# mdbt40.net
KiCad netlist of a schematic drawn in EAGLE
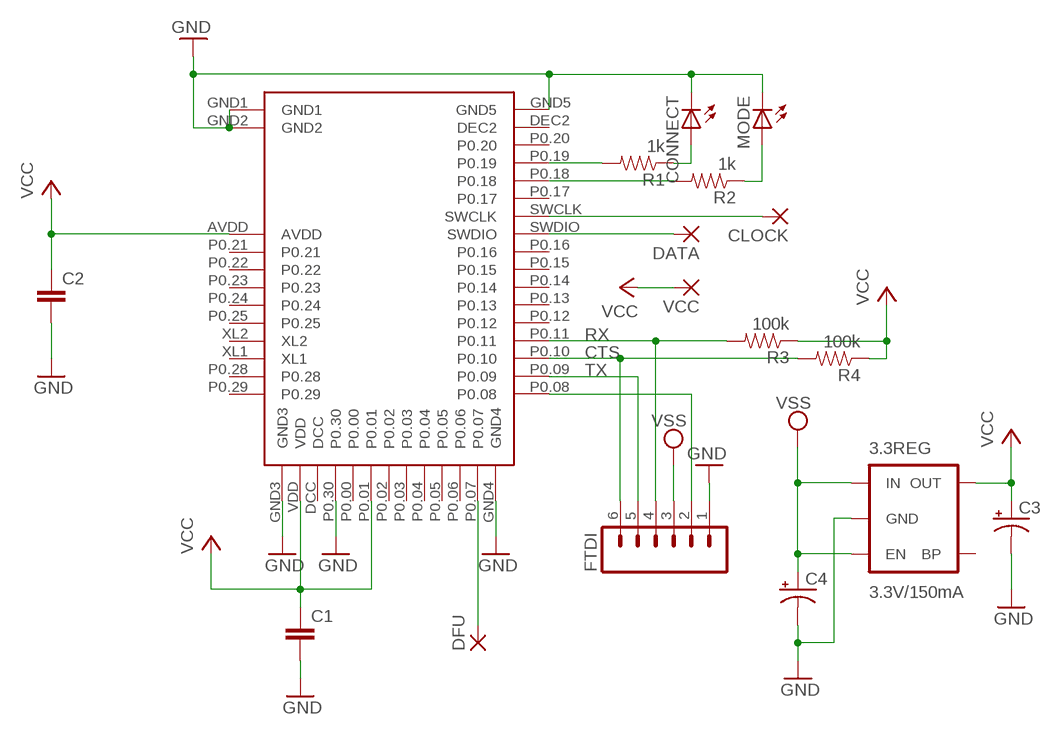
[diagram p0: schematic, sheet 1]

(export (version "E")
  (design (tool "Eeschema 10.0.6"))
  (components
    (comp (ref "3.3REG")
      (value "3.3V/150mA")
      (footprint "eagle-import:SOT23-5")
      (libsource (lib "eagle-import") (part "V_REG_MIC52053.3V"))
    )
    (comp (ref "C1")
      (value "CAP0603-CAP")
      (footprint "eagle-import:0603-CAP")
      (libsource (lib "eagle-import") (part "CAP0603-CAP"))
    )
    (comp (ref "C2")
      (value "CAP0603-CAP")
      (footprint "eagle-import:0603-CAP")
      (libsource (lib "eagle-import") (part "CAP0603-CAP"))
    )
    (comp (ref "C3")
      (value "CAP_POL1206")
      (footprint "eagle-import:EIA3216")
      (libsource (lib "eagle-import") (part "CAP_POL1206"))
    )
    (comp (ref "C4")
      (value "CAP_POL1206")
      (footprint "eagle-import:EIA3216")
      (libsource (lib "eagle-import") (part "CAP_POL1206"))
    )
    (comp (ref "CLOCK")
      (value "SMD2")
      (footprint "eagle-import:SMD1,27-2,54")
      (libsource (lib "eagle-import") (part "SMD2"))
    )
    (comp (ref "CONNECT")
      (value "LEDCHIPLED_0603")
      (footprint "eagle-import:CHIPLED_0603")
      (libsource (lib "eagle-import") (part "LEDCHIPLED_0603"))
    )
    (comp (ref "DATA")
      (value "SMD2")
      (footprint "eagle-import:SMD1,27-2,54")
      (libsource (lib "eagle-import") (part "SMD2"))
    )
    (comp (ref "DFU")
      (value "SMD2")
      (footprint "eagle-import:SMD1,27-2,54")
      (libsource (lib "eagle-import") (part "SMD2"))
    )
    (comp (ref "FTDI")
      (value "M06LONGPADS")
      (footprint "eagle-import:1X06_LONGPADS")
      (libsource (lib "eagle-import") (part "M06LONGPADS"))
    )
    (comp (ref "MODE")
      (value "LEDCHIPLED_0603")
      (footprint "eagle-import:CHIPLED_0603")
      (libsource (lib "eagle-import") (part "LEDCHIPLED_0603"))
    )
    (comp (ref "R1")
      (value "1k")
      (footprint "eagle-import:0603-RES")
      (libsource (lib "eagle-import") (part "RESISTOR0603"))
    )
    (comp (ref "R2")
      (value "1k")
      (footprint "eagle-import:0603-RES")
      (libsource (lib "eagle-import") (part "RESISTOR0603"))
    )
    (comp (ref "R3")
      (value "100k")
      (footprint "eagle-import:0603-RES")
      (libsource (lib "eagle-import") (part "RESISTOR0603"))
    )
    (comp (ref "R4")
      (value "100k")
      (footprint "eagle-import:0603-RES")
      (libsource (lib "eagle-import") (part "RESISTOR0603"))
    )
    (comp (ref "U$1")
      (value "MDBT40")
      (footprint "eagle-import:MDBT40")
      (libsource (lib "eagle-import") (part "MDBT40"))
    )
    (comp (ref "VCC")
      (value "SMD2")
      (footprint "eagle-import:SMD1,27-2,54")
      (libsource (lib "eagle-import") (part "SMD2"))
    )
  )
  (nets
    (net (code "1") (name "/CTS") (class "Default")
      (node (ref "FTDI") (pin "6") (pinfunction "6_6") (pintype "passive"))
      (node (ref "R4") (pin "2") (pinfunction "2_2") (pintype "passive"))
      (node (ref "U$1") (pin "P0.10") (pinfunction "P0.10_P0.10") (pintype "bidirectional"))
    )
    (net (code "2") (name "/RX") (class "Default")
      (node (ref "FTDI") (pin "4") (pinfunction "4_4") (pintype "passive"))
      (node (ref "R3") (pin "2") (pinfunction "2_2") (pintype "passive"))
      (node (ref "U$1") (pin "P0.11") (pinfunction "P0.11_P0.11") (pintype "bidirectional"))
    )
    (net (code "3") (name "/TX") (class "Default")
      (node (ref "FTDI") (pin "5") (pinfunction "5_5") (pintype "passive"))
      (node (ref "U$1") (pin "P0.09") (pinfunction "P0.09_P0.09") (pintype "bidirectional"))
    )
    (net (code "4") (name "GND") (class "Default")
      (node (ref "3.3REG") (pin "2") (pinfunction "GND_2") (pintype "input"))
      (node (ref "C1") (pin "2") (pinfunction "2_2") (pintype "passive"))
      (node (ref "C2") (pin "2") (pinfunction "2_2") (pintype "passive"))
      (node (ref "C3") (pin "C") (pinfunction "-_C") (pintype "passive"))
      (node (ref "C4") (pin "C") (pinfunction "-_C") (pintype "passive"))
      (node (ref "CONNECT") (pin "C") (pinfunction "C_C") (pintype "passive"))
      (node (ref "FTDI") (pin "1") (pinfunction "1_1") (pintype "passive"))
      (node (ref "MODE") (pin "C") (pinfunction "C_C") (pintype "passive"))
      (node (ref "U$1") (pin "GND1") (pinfunction "GND1_GND1") (pintype "bidirectional"))
      (node (ref "U$1") (pin "GND2") (pinfunction "GND2_GND2") (pintype "bidirectional"))
      (node (ref "U$1") (pin "GND3") (pinfunction "GND3_GND3") (pintype "bidirectional"))
      (node (ref "U$1") (pin "GND4") (pinfunction "GND4_GND4") (pintype "bidirectional"))
      (node (ref "U$1") (pin "GND5") (pinfunction "GND5_GND5") (pintype "bidirectional"))
      (node (ref "U$1") (pin "P0.30") (pinfunction "P0.30_P0.30") (pintype "bidirectional"))
    )
    (net (code "5") (name "Net-(CLOCK-P)") (class "Default")
      (node (ref "CLOCK") (pin "1") (pinfunction "P_1") (pintype "passive"))
      (node (ref "U$1") (pin "SWCLK") (pinfunction "SWCLK_SWCLK") (pintype "bidirectional"))
    )
    (net (code "6") (name "Net-(CONNECT-PadA)") (class "Default")
      (node (ref "CONNECT") (pin "A") (pinfunction "A_A") (pintype "passive"))
      (node (ref "R1") (pin "1") (pinfunction "1_1") (pintype "passive"))
    )
    (net (code "7") (name "Net-(DATA-P)") (class "Default")
      (node (ref "DATA") (pin "1") (pinfunction "P_1") (pintype "passive"))
      (node (ref "U$1") (pin "SWDIO") (pinfunction "SWDIO_SWDIO") (pintype "bidirectional"))
    )
    (net (code "8") (name "Net-(DFU-P)") (class "Default")
      (node (ref "DFU") (pin "1") (pinfunction "P_1") (pintype "passive"))
      (node (ref "U$1") (pin "P0.07") (pinfunction "P0.07_P0.07") (pintype "bidirectional"))
    )
    (net (code "9") (name "Net-(FTDI-Pad2)") (class "Default")
      (node (ref "FTDI") (pin "2") (pinfunction "2_2") (pintype "passive"))
      (node (ref "U$1") (pin "P0.08") (pinfunction "P0.08_P0.08") (pintype "bidirectional"))
    )
    (net (code "10") (name "Net-(MODE-PadA)") (class "Default")
      (node (ref "MODE") (pin "A") (pinfunction "A_A") (pintype "passive"))
      (node (ref "R2") (pin "1") (pinfunction "1_1") (pintype "passive"))
    )
    (net (code "11") (name "Net-(R1-Pad2)") (class "Default")
      (node (ref "R1") (pin "2") (pinfunction "2_2") (pintype "passive"))
      (node (ref "U$1") (pin "P0.19") (pinfunction "P0.19_P0.19") (pintype "bidirectional"))
    )
    (net (code "12") (name "Net-(R2-Pad2)") (class "Default")
      (node (ref "R2") (pin "2") (pinfunction "2_2") (pintype "passive"))
      (node (ref "U$1") (pin "P0.18") (pinfunction "P0.18_P0.18") (pintype "bidirectional"))
    )
    (net (code "13") (name "VCC") (class "Default")
      (node (ref "3.3REG") (pin "5") (pinfunction "OUT_5") (pintype "passive"))
      (node (ref "C1") (pin "1") (pinfunction "1_1") (pintype "passive"))
      (node (ref "C2") (pin "1") (pinfunction "1_1") (pintype "passive"))
      (node (ref "C3") (pin "A") (pinfunction "+_A") (pintype "passive"))
      (node (ref "R3") (pin "1") (pinfunction "1_1") (pintype "passive"))
      (node (ref "R4") (pin "1") (pinfunction "1_1") (pintype "passive"))
      (node (ref "U$1") (pin "AVDD") (pinfunction "AVDD_AVDD") (pintype "bidirectional"))
      (node (ref "U$1") (pin "P0.01") (pinfunction "P0.01_P0.01") (pintype "bidirectional"))
      (node (ref "U$1") (pin "VDD") (pinfunction "VDD_VDD") (pintype "bidirectional"))
      (node (ref "VCC") (pin "1") (pinfunction "P_1") (pintype "passive"))
    )
    (net (code "14") (name "VSS") (class "Default")
      (node (ref "3.3REG") (pin "1") (pinfunction "IN_1") (pintype "input"))
      (node (ref "3.3REG") (pin "3") (pinfunction "EN_3") (pintype "input"))
      (node (ref "C4") (pin "A") (pinfunction "+_A") (pintype "passive"))
      (node (ref "FTDI") (pin "3") (pinfunction "3_3") (pintype "passive"))
    )
    (net (code "15") (name "unconnected-(3.3REG-BP-Pad4)") (class "Default")
      (node (ref "3.3REG") (pin "4") (pinfunction "BP_4") (pintype "input"))
    )
    (net (code "16") (name "unconnected-(U$1-PadDCC)") (class "Default")
      (node (ref "U$1") (pin "DCC") (pinfunction "DCC_DCC") (pintype "bidirectional"))
    )
    (net (code "17") (name "unconnected-(U$1-PadDEC2)") (class "Default")
      (node (ref "U$1") (pin "DEC2") (pinfunction "DEC2_DEC2") (pintype "bidirectional"))
    )
    (net (code "18") (name "unconnected-(U$1-PadP0.00)") (class "Default")
      (node (ref "U$1") (pin "P0.00") (pinfunction "P0.00_P0.00") (pintype "bidirectional"))
    )
    (net (code "19") (name "unconnected-(U$1-PadP0.02)") (class "Default")
      (node (ref "U$1") (pin "P0.02") (pinfunction "P0.02_P0.02") (pintype "bidirectional"))
    )
    (net (code "20") (name "unconnected-(U$1-PadP0.03)") (class "Default")
      (node (ref "U$1") (pin "P0.03") (pinfunction "P0.03_P0.03") (pintype "bidirectional"))
    )
    (net (code "21") (name "unconnected-(U$1-PadP0.04)") (class "Default")
      (node (ref "U$1") (pin "P0.04") (pinfunction "P0.04_P0.04") (pintype "bidirectional"))
    )
    (net (code "22") (name "unconnected-(U$1-PadP0.05)") (class "Default")
      (node (ref "U$1") (pin "P0.05") (pinfunction "P0.05_P0.05") (pintype "bidirectional"))
    )
    (net (code "23") (name "unconnected-(U$1-PadP0.06)") (class "Default")
      (node (ref "U$1") (pin "P0.06") (pinfunction "P0.06_P0.06") (pintype "bidirectional"))
    )
    (net (code "24") (name "unconnected-(U$1-PadP0.12)") (class "Default")
      (node (ref "U$1") (pin "P0.12") (pinfunction "P0.12_P0.12") (pintype "bidirectional"))
    )
    (net (code "25") (name "unconnected-(U$1-PadP0.13)") (class "Default")
      (node (ref "U$1") (pin "P0.13") (pinfunction "P0.13_P0.13") (pintype "bidirectional"))
    )
    (net (code "26") (name "unconnected-(U$1-PadP0.14)") (class "Default")
      (node (ref "U$1") (pin "P0.14") (pinfunction "P0.14_P0.14") (pintype "bidirectional"))
    )
    (net (code "27") (name "unconnected-(U$1-PadP0.15)") (class "Default")
      (node (ref "U$1") (pin "P0.15") (pinfunction "P0.15_P0.15") (pintype "bidirectional"))
    )
    (net (code "28") (name "unconnected-(U$1-PadP0.16)") (class "Default")
      (node (ref "U$1") (pin "P0.16") (pinfunction "P0.16_P0.16") (pintype "bidirectional"))
    )
    (net (code "29") (name "unconnected-(U$1-PadP0.17)") (class "Default")
      (node (ref "U$1") (pin "P0.17") (pinfunction "P0.17_P0.17") (pintype "bidirectional"))
    )
    (net (code "30") (name "unconnected-(U$1-PadP0.20)") (class "Default")
      (node (ref "U$1") (pin "P0.20") (pinfunction "P0.20_P0.20") (pintype "bidirectional"))
    )
    (net (code "31") (name "unconnected-(U$1-PadP0.21)") (class "Default")
      (node (ref "U$1") (pin "P0.21") (pinfunction "P0.21_P0.21") (pintype "bidirectional"))
    )
    (net (code "32") (name "unconnected-(U$1-PadP0.22)") (class "Default")
      (node (ref "U$1") (pin "P0.22") (pinfunction "P0.22_P0.22") (pintype "bidirectional"))
    )
    (net (code "33") (name "unconnected-(U$1-PadP0.23)") (class "Default")
      (node (ref "U$1") (pin "P0.23") (pinfunction "P0.23_P0.23") (pintype "bidirectional"))
    )
    (net (code "34") (name "unconnected-(U$1-PadP0.24)") (class "Default")
      (node (ref "U$1") (pin "P0.24") (pinfunction "P0.24_P0.24") (pintype "bidirectional"))
    )
    (net (code "35") (name "unconnected-(U$1-PadP0.25)") (class "Default")
      (node (ref "U$1") (pin "P0.25") (pinfunction "P0.25_P0.25") (pintype "bidirectional"))
    )
    (net (code "36") (name "unconnected-(U$1-PadP0.28)") (class "Default")
      (node (ref "U$1") (pin "P0.28") (pinfunction "P0.28_P0.28") (pintype "bidirectional"))
    )
    (net (code "37") (name "unconnected-(U$1-PadP0.29)") (class "Default")
      (node (ref "U$1") (pin "P0.29") (pinfunction "P0.29_P0.29") (pintype "bidirectional"))
    )
    (net (code "38") (name "unconnected-(U$1-PadXL1)") (class "Default")
      (node (ref "U$1") (pin "XL1") (pinfunction "XL1_XL1") (pintype "bidirectional"))
    )
    (net (code "39") (name "unconnected-(U$1-PadXL2)") (class "Default")
      (node (ref "U$1") (pin "XL2") (pinfunction "XL2_XL2") (pintype "bidirectional"))
    )
  )
)
